# 5_TTY.net
KiCad netlist of a schematic drawn in EAGLE
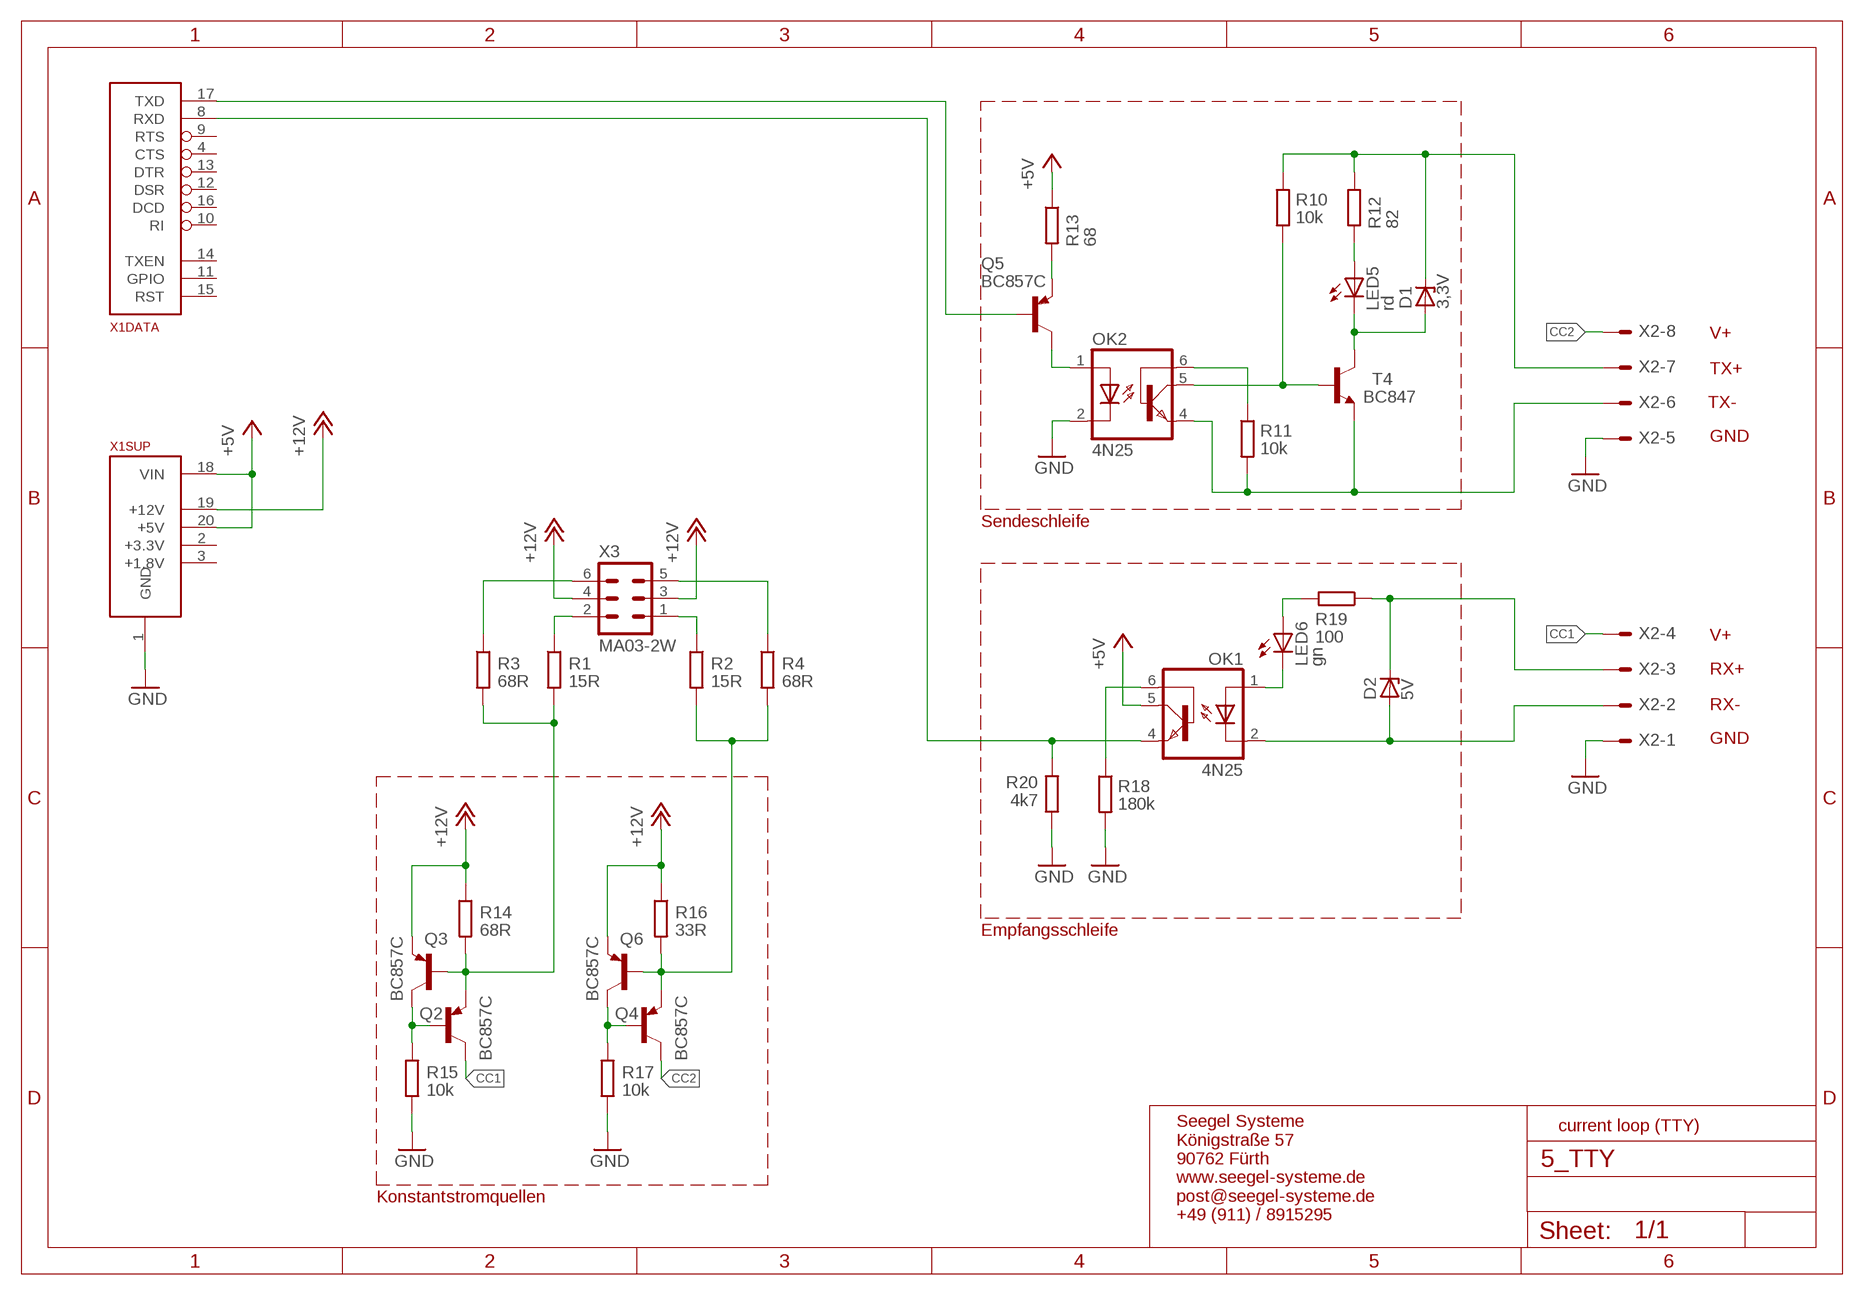
[diagram p0: schematic, sheet 1]

(export (version "E")
  (design (tool "Eeschema 10.0.6"))
  (components
    (comp (ref "D1")
      (value "3,3V")
      (footprint "eagle-import:SOT23")
      (libsource (lib "eagle-import") (part "ZENER-DIODESOT23"))
    )
    (comp (ref "D2")
      (value "5V")
      (footprint "eagle-import:SOT23")
      (libsource (lib "eagle-import") (part "ZENER-DIODESOT23"))
    )
    (comp (ref "LED5")
      (value "rd")
      (footprint "eagle-import:CHIPLED_0603")
      (libsource (lib "eagle-import") (part "LEDCHIPLED_0603"))
    )
    (comp (ref "LED6")
      (value "gn")
      (footprint "eagle-import:CHIPLED_0603")
      (libsource (lib "eagle-import") (part "LEDCHIPLED_0603"))
    )
    (comp (ref "OK1")
      (value "4N25")
      (footprint "eagle-import:DIL06")
      (fields (field (name "MF") "FAIRCHILD SEMICONDUCTOR") (field (name "MPN") "4N35"))
      (libsource (lib "eagle-import") (part "4N35"))
    )
    (comp (ref "OK2")
      (value "4N25")
      (footprint "eagle-import:DIL06")
      (fields (field (name "MF") "FAIRCHILD SEMICONDUCTOR") (field (name "MPN") "4N35"))
      (libsource (lib "eagle-import") (part "4N35"))
    )
    (comp (ref "Q2")
      (value "BC857C")
      (footprint "eagle-import:SOT23-BEC")
      (libsource (lib "eagle-import") (part "BC857SMDC"))
    )
    (comp (ref "Q3")
      (value "BC857C")
      (footprint "eagle-import:SOT23-BEC")
      (libsource (lib "eagle-import") (part "BC857SMDC"))
    )
    (comp (ref "Q4")
      (value "BC857C")
      (footprint "eagle-import:SOT23-BEC")
      (libsource (lib "eagle-import") (part "BC857SMDC"))
    )
    (comp (ref "Q5")
      (value "BC857C")
      (footprint "eagle-import:SOT23-BEC")
      (libsource (lib "eagle-import") (part "BC857SMDC"))
    )
    (comp (ref "Q6")
      (value "BC857C")
      (footprint "eagle-import:SOT23-BEC")
      (libsource (lib "eagle-import") (part "BC857SMDC"))
    )
    (comp (ref "R1")
      (value "15R")
      (footprint "eagle-import:R0805")
      (libsource (lib "eagle-import") (part "R-EU_R0805"))
    )
    (comp (ref "R2")
      (value "15R")
      (footprint "eagle-import:R0805")
      (libsource (lib "eagle-import") (part "R-EU_R0805"))
    )
    (comp (ref "R3")
      (value "68R")
      (footprint "eagle-import:R0805")
      (libsource (lib "eagle-import") (part "R-EU_R0805"))
    )
    (comp (ref "R4")
      (value "68R")
      (footprint "eagle-import:R0805")
      (libsource (lib "eagle-import") (part "R-EU_R0805"))
    )
    (comp (ref "R10")
      (value "10k")
      (footprint "eagle-import:R0805")
      (libsource (lib "eagle-import") (part "R-EU_R0805"))
    )
    (comp (ref "R11")
      (value "10k")
      (footprint "eagle-import:R0805")
      (libsource (lib "eagle-import") (part "R-EU_R0805"))
    )
    (comp (ref "R12")
      (value "82")
      (footprint "eagle-import:R0805")
      (libsource (lib "eagle-import") (part "R-EU_R0805"))
    )
    (comp (ref "R13")
      (value "68")
      (footprint "eagle-import:R0805")
      (libsource (lib "eagle-import") (part "R-EU_R0805"))
    )
    (comp (ref "R14")
      (value "68R")
      (footprint "eagle-import:R0805")
      (libsource (lib "eagle-import") (part "R-EU_R0805"))
    )
    (comp (ref "R15")
      (value "10k")
      (footprint "eagle-import:R0805")
      (libsource (lib "eagle-import") (part "R-EU_R0805"))
    )
    (comp (ref "R16")
      (value "33R")
      (footprint "eagle-import:R0805")
      (libsource (lib "eagle-import") (part "R-EU_R0805"))
    )
    (comp (ref "R17")
      (value "10k")
      (footprint "eagle-import:R0805")
      (libsource (lib "eagle-import") (part "R-EU_R0805"))
    )
    (comp (ref "R18")
      (value "180k")
      (footprint "eagle-import:R0805")
      (libsource (lib "eagle-import") (part "R-EU_R0805"))
    )
    (comp (ref "R19")
      (value "100")
      (footprint "eagle-import:R0805")
      (libsource (lib "eagle-import") (part "R-EU_R0805"))
    )
    (comp (ref "R20")
      (value "4k7")
      (footprint "eagle-import:R0805")
      (libsource (lib "eagle-import") (part "R-EU_R0805"))
    )
    (comp (ref "T4")
      (value "BC847")
      (footprint "eagle-import:SOT23")
      (libsource (lib "eagle-import") (part "BC847"))
    )
    (comp (ref "X1")
      (value "ALLSERIALSLAVE")
      (footprint "eagle-import:DAUGHTER-THT")
      (libsource (lib "eagle-import") (part "ALLSERIALSLAVE"))
    )
    (comp (ref "X2")
      (value "AKL18X-08W")
      (footprint "eagle-import:AKL182-08")
      (libsource (lib "eagle-import") (part "AKL18X-08W"))
    )
    (comp (ref "X3")
      (value "MA03-2W")
      (footprint "eagle-import:MA03-2W")
      (libsource (lib "eagle-import") (part "MA03-2W"))
    )
  )
  (nets
    (net (code "1") (name "+5V") (class "Default")
      (node (ref "OK1") (pin "5") (pinfunction "COL_5") (pintype "passive"))
      (node (ref "R13") (pin "1") (pinfunction "1_1") (pintype "passive"))
      (node (ref "X1") (pin "18") (pinfunction "VIN_18") (pintype "bidirectional"))
      (node (ref "X1") (pin "20") (pinfunction "+5V_20") (pintype "bidirectional"))
    )
    (net (code "2") (name "+12V") (class "Default")
      (node (ref "Q3") (pin "E") (pinfunction "E_E") (pintype "passive"))
      (node (ref "Q6") (pin "E") (pinfunction "E_E") (pintype "passive"))
      (node (ref "R14") (pin "1") (pinfunction "1_1") (pintype "passive"))
      (node (ref "R16") (pin "1") (pinfunction "1_1") (pintype "passive"))
      (node (ref "X1") (pin "19") (pinfunction "+12V_19") (pintype "bidirectional"))
      (node (ref "X3") (pin "3") (pinfunction "3_3") (pintype "passive"))
      (node (ref "X3") (pin "4") (pinfunction "4_4") (pintype "passive"))
    )
    (net (code "3") (name "CC1") (class "Default")
      (node (ref "Q2") (pin "C") (pinfunction "C_C") (pintype "passive"))
      (node (ref "X2") (pin "P$4") (pinfunction "S_P$4") (pintype "passive"))
    )
    (net (code "4") (name "CC2") (class "Default")
      (node (ref "Q4") (pin "C") (pinfunction "C_C") (pintype "passive"))
      (node (ref "X2") (pin "P$8") (pinfunction "S_P$8") (pintype "passive"))
    )
    (net (code "5") (name "GND") (class "Default")
      (node (ref "OK2") (pin "2") (pinfunction "C_2") (pintype "passive"))
      (node (ref "R15") (pin "1") (pinfunction "1_1") (pintype "passive"))
      (node (ref "R17") (pin "1") (pinfunction "1_1") (pintype "passive"))
      (node (ref "R18") (pin "2") (pinfunction "2_2") (pintype "passive"))
      (node (ref "R20") (pin "1") (pinfunction "1_1") (pintype "passive"))
      (node (ref "X1") (pin "1") (pinfunction "GND_1") (pintype "bidirectional"))
      (node (ref "X2") (pin "P$1") (pinfunction "S_P$1") (pintype "passive"))
      (node (ref "X2") (pin "P$5") (pinfunction "S_P$5") (pintype "passive"))
    )
    (net (code "6") (name "Net-(D1-A)") (class "Default")
      (node (ref "D1") (pin "1") (pinfunction "A_1") (pintype "passive"))
      (node (ref "LED5") (pin "C") (pinfunction "C_C") (pintype "passive"))
      (node (ref "T4") (pin "3") (pinfunction "C_3") (pintype "passive"))
    )
    (net (code "7") (name "Net-(D1-C)") (class "Default")
      (node (ref "D1") (pin "3") (pinfunction "C_3") (pintype "passive"))
      (node (ref "R10") (pin "1") (pinfunction "1_1") (pintype "passive"))
      (node (ref "R12") (pin "1") (pinfunction "1_1") (pintype "passive"))
      (node (ref "X2") (pin "P$7") (pinfunction "S_P$7") (pintype "passive"))
    )
    (net (code "8") (name "Net-(D2-A)") (class "Default")
      (node (ref "D2") (pin "1") (pinfunction "A_1") (pintype "passive"))
      (node (ref "OK1") (pin "2") (pinfunction "C_2") (pintype "passive"))
      (node (ref "X2") (pin "P$2") (pinfunction "S_P$2") (pintype "passive"))
    )
    (net (code "9") (name "Net-(D2-C)") (class "Default")
      (node (ref "D2") (pin "3") (pinfunction "C_3") (pintype "passive"))
      (node (ref "R19") (pin "1") (pinfunction "1_1") (pintype "passive"))
      (node (ref "X2") (pin "P$3") (pinfunction "S_P$3") (pintype "passive"))
    )
    (net (code "10") (name "Net-(LED5-PadA)") (class "Default")
      (node (ref "LED5") (pin "A") (pinfunction "A_A") (pintype "passive"))
      (node (ref "R12") (pin "2") (pinfunction "2_2") (pintype "passive"))
    )
    (net (code "11") (name "Net-(LED6-PadA)") (class "Default")
      (node (ref "LED6") (pin "A") (pinfunction "A_A") (pintype "passive"))
      (node (ref "R19") (pin "2") (pinfunction "2_2") (pintype "passive"))
    )
    (net (code "12") (name "Net-(OK1-A)") (class "Default")
      (node (ref "LED6") (pin "C") (pinfunction "C_C") (pintype "passive"))
      (node (ref "OK1") (pin "1") (pinfunction "A_1") (pintype "passive"))
    )
    (net (code "13") (name "Net-(OK1-BAS)") (class "Default")
      (node (ref "OK1") (pin "6") (pinfunction "BAS_6") (pintype "passive"))
      (node (ref "R18") (pin "1") (pinfunction "1_1") (pintype "passive"))
    )
    (net (code "14") (name "Net-(OK1-EMI)") (class "Default")
      (node (ref "OK1") (pin "4") (pinfunction "EMI_4") (pintype "passive"))
      (node (ref "R20") (pin "2") (pinfunction "2_2") (pintype "passive"))
      (node (ref "X1") (pin "8") (pinfunction "RXD_8") (pintype "input"))
    )
    (net (code "15") (name "Net-(OK2-A)") (class "Default")
      (node (ref "OK2") (pin "1") (pinfunction "A_1") (pintype "passive"))
      (node (ref "Q5") (pin "C") (pinfunction "C_C") (pintype "passive"))
    )
    (net (code "16") (name "Net-(OK2-BAS)") (class "Default")
      (node (ref "OK2") (pin "6") (pinfunction "BAS_6") (pintype "passive"))
      (node (ref "R11") (pin "1") (pinfunction "1_1") (pintype "passive"))
    )
    (net (code "17") (name "Net-(OK2-COL)") (class "Default")
      (node (ref "OK2") (pin "5") (pinfunction "COL_5") (pintype "passive"))
      (node (ref "R10") (pin "2") (pinfunction "2_2") (pintype "passive"))
      (node (ref "T4") (pin "1") (pinfunction "B_1") (pintype "passive"))
    )
    (net (code "18") (name "Net-(OK2-EMI)") (class "Default")
      (node (ref "OK2") (pin "4") (pinfunction "EMI_4") (pintype "passive"))
      (node (ref "R11") (pin "2") (pinfunction "2_2") (pintype "passive"))
      (node (ref "T4") (pin "2") (pinfunction "E_2") (pintype "passive"))
      (node (ref "X2") (pin "P$6") (pinfunction "S_P$6") (pintype "passive"))
    )
    (net (code "19") (name "Net-(Q2-PadB)") (class "Default")
      (node (ref "Q2") (pin "B") (pinfunction "B_B") (pintype "passive"))
      (node (ref "Q3") (pin "C") (pinfunction "C_C") (pintype "passive"))
      (node (ref "R15") (pin "2") (pinfunction "2_2") (pintype "passive"))
    )
    (net (code "20") (name "Net-(Q2-PadE)") (class "Default")
      (node (ref "Q2") (pin "E") (pinfunction "E_E") (pintype "passive"))
      (node (ref "Q3") (pin "B") (pinfunction "B_B") (pintype "passive"))
      (node (ref "R1") (pin "2") (pinfunction "2_2") (pintype "passive"))
      (node (ref "R14") (pin "2") (pinfunction "2_2") (pintype "passive"))
      (node (ref "R3") (pin "2") (pinfunction "2_2") (pintype "passive"))
    )
    (net (code "21") (name "Net-(Q4-PadB)") (class "Default")
      (node (ref "Q4") (pin "B") (pinfunction "B_B") (pintype "passive"))
      (node (ref "Q6") (pin "C") (pinfunction "C_C") (pintype "passive"))
      (node (ref "R17") (pin "2") (pinfunction "2_2") (pintype "passive"))
    )
    (net (code "22") (name "Net-(Q4-PadE)") (class "Default")
      (node (ref "Q4") (pin "E") (pinfunction "E_E") (pintype "passive"))
      (node (ref "Q6") (pin "B") (pinfunction "B_B") (pintype "passive"))
      (node (ref "R16") (pin "2") (pinfunction "2_2") (pintype "passive"))
      (node (ref "R2") (pin "2") (pinfunction "2_2") (pintype "passive"))
      (node (ref "R4") (pin "2") (pinfunction "2_2") (pintype "passive"))
    )
    (net (code "23") (name "Net-(Q5-PadE)") (class "Default")
      (node (ref "Q5") (pin "E") (pinfunction "E_E") (pintype "passive"))
      (node (ref "R13") (pin "2") (pinfunction "2_2") (pintype "passive"))
    )
    (net (code "24") (name "Net-(R1-Pad1)") (class "Default")
      (node (ref "R1") (pin "1") (pinfunction "1_1") (pintype "passive"))
      (node (ref "X3") (pin "2") (pinfunction "2_2") (pintype "passive"))
    )
    (net (code "25") (name "Net-(R2-Pad1)") (class "Default")
      (node (ref "R2") (pin "1") (pinfunction "1_1") (pintype "passive"))
      (node (ref "X3") (pin "1") (pinfunction "1_1") (pintype "passive"))
    )
    (net (code "26") (name "Net-(R3-Pad1)") (class "Default")
      (node (ref "R3") (pin "1") (pinfunction "1_1") (pintype "passive"))
      (node (ref "X3") (pin "6") (pinfunction "6_6") (pintype "passive"))
    )
    (net (code "27") (name "Net-(R4-Pad1)") (class "Default")
      (node (ref "R4") (pin "1") (pinfunction "1_1") (pintype "passive"))
      (node (ref "X3") (pin "5") (pinfunction "5_5") (pintype "passive"))
    )
    (net (code "28") (name "Net-(X1A-TXD)") (class "Default")
      (node (ref "Q5") (pin "B") (pinfunction "B_B") (pintype "passive"))
      (node (ref "X1") (pin "17") (pinfunction "TXD_17") (pintype "output"))
    )
    (net (code "29") (name "unconnected-(X1A-CTS-Pad4)") (class "Default")
      (node (ref "X1") (pin "4") (pinfunction "CTS_4") (pintype "input"))
    )
    (net (code "30") (name "unconnected-(X1A-DCD-Pad16)") (class "Default")
      (node (ref "X1") (pin "16") (pinfunction "DCD_16") (pintype "input"))
    )
    (net (code "31") (name "unconnected-(X1A-DSR-Pad12)") (class "Default")
      (node (ref "X1") (pin "12") (pinfunction "DSR_12") (pintype "input"))
    )
    (net (code "32") (name "unconnected-(X1A-DTR-Pad13)") (class "Default")
      (node (ref "X1") (pin "13") (pinfunction "DTR_13") (pintype "output"))
    )
    (net (code "33") (name "unconnected-(X1A-GPIO-Pad11)") (class "Default")
      (node (ref "X1") (pin "11") (pinfunction "GPIO_11") (pintype "bidirectional"))
    )
    (net (code "34") (name "unconnected-(X1A-RI-Pad10)") (class "Default")
      (node (ref "X1") (pin "10") (pinfunction "RI_10") (pintype "input"))
    )
    (net (code "35") (name "unconnected-(X1A-RST-Pad15)") (class "Default")
      (node (ref "X1") (pin "15") (pinfunction "RST_15") (pintype "bidirectional"))
    )
    (net (code "36") (name "unconnected-(X1A-RTS-Pad9)") (class "Default")
      (node (ref "X1") (pin "9") (pinfunction "RTS_9") (pintype "output"))
    )
    (net (code "37") (name "unconnected-(X1A-TXEN-Pad14)") (class "Default")
      (node (ref "X1") (pin "14") (pinfunction "TXEN_14") (pintype "output"))
    )
    (net (code "38") (name "unconnected-(X1B-+1.8V-Pad3)") (class "Default")
      (node (ref "X1") (pin "3") (pinfunction "+1.8V_3") (pintype "bidirectional"))
    )
    (net (code "39") (name "unconnected-(X1B-+3.3V-Pad2)") (class "Default")
      (node (ref "X1") (pin "2") (pinfunction "+3.3V_2") (pintype "bidirectional"))
    )
  )
)
